# ETH_microSD.net
KiCad netlist of a schematic drawn in Altium Designer
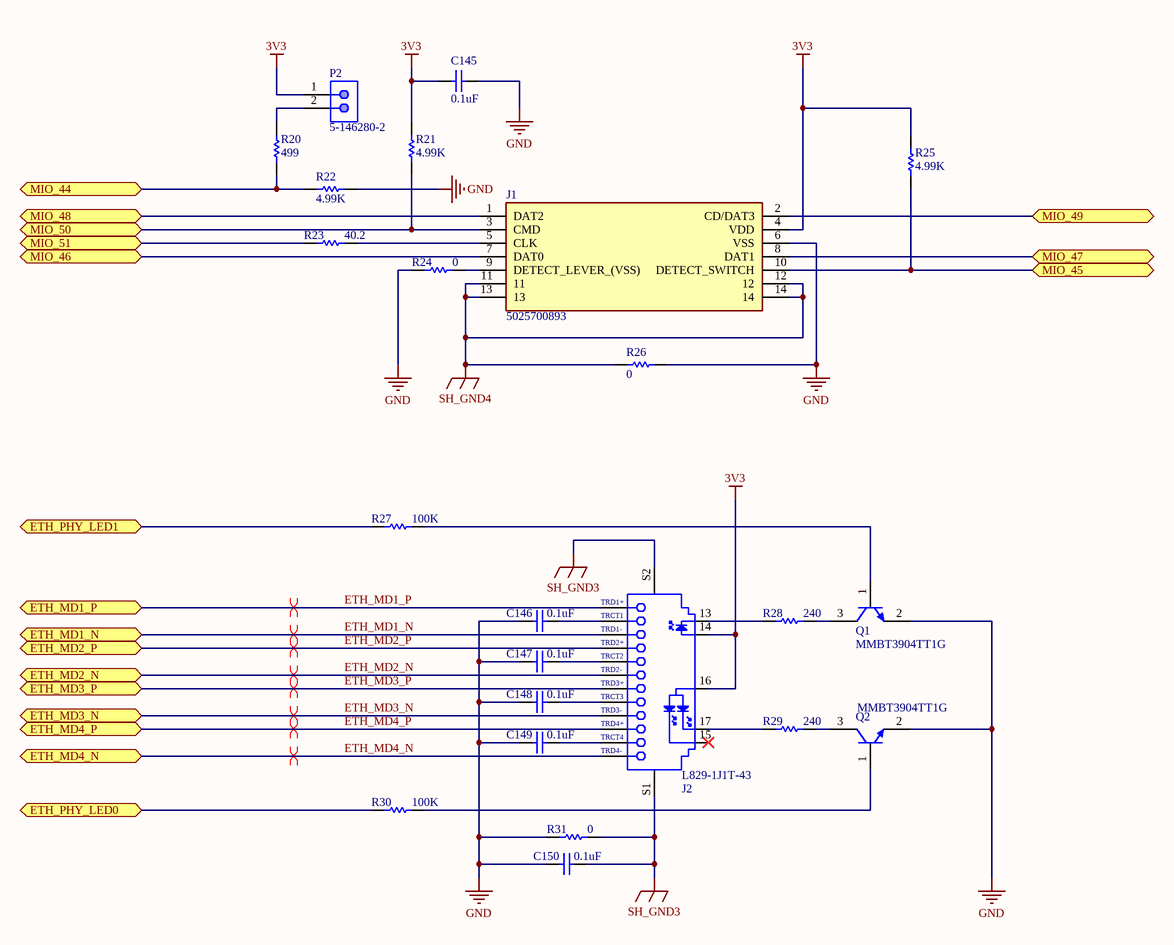
[diagram p0: ETH_microSD.SchDoc]

(export (version "E")
  (design (tool "Eeschema 10.0.6"))
  (components
    (comp (ref "C145")
      (value "0.1uF")
      (footprint "CAPC0201(0603)33_N")
      (libsource (lib "my_schsymbols") (part "CAP_0201"))
    )
    (comp (ref "C146")
      (value "0.1uF")
      (footprint "CAPC0201(0603)33_N")
      (libsource (lib "my_schsymbols") (part "CAP_0201"))
    )
    (comp (ref "C147")
      (value "0.1uF")
      (footprint "CAPC0201(0603)33_N")
      (libsource (lib "my_schsymbols") (part "CAP_0201"))
    )
    (comp (ref "C148")
      (value "0.1uF")
      (footprint "CAPC0201(0603)33_N")
      (libsource (lib "my_schsymbols") (part "CAP_0201"))
    )
    (comp (ref "C149")
      (value "0.1uF")
      (footprint "CAPC0201(0603)33_N")
      (libsource (lib "my_schsymbols") (part "CAP_0201"))
    )
    (comp (ref "C150")
      (value "0.1uF")
      (footprint "CAPC0201(0603)33_N")
      (libsource (lib "my_schsymbols") (part "CAP_0201"))
    )
    (comp (ref "J1")
      (value "5025700893")
      (footprint "5025700893")
      (description "Connector")
      (libsource (lib "altium-import") (part "root_0_5025700893_"))
    )
    (comp (ref "J2")
      (value "L829-1J1T-43")
      (footprint "BELS-L829-1J1T-43_V")
      (description "Gigabit MagJack(R) Ultra Low Profile, 10/100/1000 Base-T, 19-Pin THD, RoHS, Tray")
      (libsource (lib "Altium Content Vault") (part "RJ45-17-2SHLD"))
    )
    (comp (ref "P2")
      (value "5-146280-2")
      (footprint "TECO-5-146280-2_V")
      (fields (field (name "MANUFACTURER") "TE Connectivity"))
      (libsource (lib "Altium Content Vault") (part "CN-1P-M-R2"))
    )
    (comp (ref "Q1")
      (value "MMBT3904TT1G")
      (footprint "ONSC-SC-75-3-463-01_V")
      (description "General Purpose Transistor, NPN Silicon, 3-Pin SC-75, Pb-Free, Tape and Reel")
      (fields (field (name "MANUFACTURER") "On Semiconductor"))
      (libsource (lib "Altium Content Vault") (part "ONSC-NPN-B1E2C3-3"))
    )
    (comp (ref "Q2")
      (value "MMBT3904TT1G")
      (footprint "ONSC-SC-75-3-463-01_V")
      (description "General Purpose Transistor, NPN Silicon, 3-Pin SC-75, Pb-Free, Tape and Reel")
      (fields (field (name "MANUFACTURER") "On Semiconductor"))
      (libsource (lib "Altium Content Vault") (part "ONSC-NPN-B1E2C3-3"))
    )
    (comp (ref "R20")
      (value "499")
      (footprint "RESC0402(1005)_N")
      (libsource (lib "my_schsymbols") (part "RES_0402"))
    )
    (comp (ref "R21")
      (value "4.99K")
      (footprint "RESC0402(1005)_N")
      (libsource (lib "my_schsymbols") (part "RES_0402"))
    )
    (comp (ref "R22")
      (value "4.99K")
      (footprint "RESC0402(1005)_N")
      (libsource (lib "my_schsymbols") (part "RES_0402"))
    )
    (comp (ref "R23")
      (value "40.2")
      (footprint "RESC0402(1005)_N")
      (libsource (lib "my_schsymbols") (part "RES_0402"))
    )
    (comp (ref "R24")
      (value "0")
      (footprint "RESC0402(1005)_N")
      (libsource (lib "my_schsymbols") (part "RES_0402"))
    )
    (comp (ref "R25")
      (value "4.99K")
      (footprint "RESC0402(1005)_N")
      (libsource (lib "my_schsymbols") (part "RES_0402"))
    )
    (comp (ref "R26")
      (value "0")
      (footprint "RESC0402(1005)_N")
      (libsource (lib "my_schsymbols") (part "RES_0402"))
    )
    (comp (ref "R27")
      (value "100K")
      (footprint "RESC0402(1005)_N")
      (libsource (lib "my_schsymbols") (part "RES_0402"))
    )
    (comp (ref "R28")
      (value "240")
      (footprint "RESC0402(1005)_N")
      (libsource (lib "my_schsymbols") (part "RES_0402"))
    )
    (comp (ref "R29")
      (value "240")
      (footprint "RESC0402(1005)_N")
      (libsource (lib "my_schsymbols") (part "RES_0402"))
    )
    (comp (ref "R30")
      (value "100K")
      (footprint "RESC0402(1005)_N")
      (libsource (lib "my_schsymbols") (part "RES_0402"))
    )
    (comp (ref "R31")
      (value "0")
      (footprint "RESC0402(1005)_N")
      (libsource (lib "my_schsymbols") (part "RES_0402"))
    )
  )
  (nets
    (net (code "1") (name "/ETH_MD1_N") (class "Default")
      (node (ref "J2") (pin "3") (pinfunction "TRD1-_3") (pintype "passive"))
    )
    (net (code "2") (name "/ETH_MD1_P") (class "Default")
      (node (ref "J2") (pin "1") (pinfunction "TRD1+_1") (pintype "passive"))
    )
    (net (code "3") (name "/ETH_MD2_N") (class "Default")
      (node (ref "J2") (pin "6") (pinfunction "TRD2-_6") (pintype "passive"))
    )
    (net (code "4") (name "/ETH_MD2_P") (class "Default")
      (node (ref "J2") (pin "4") (pinfunction "TRD2+_4") (pintype "passive"))
    )
    (net (code "5") (name "/ETH_MD3_N") (class "Default")
      (node (ref "J2") (pin "9") (pinfunction "TRD3-_9") (pintype "passive"))
    )
    (net (code "6") (name "/ETH_MD3_P") (class "Default")
      (node (ref "J2") (pin "7") (pinfunction "TRD3+_7") (pintype "passive"))
    )
    (net (code "7") (name "/ETH_MD4_N") (class "Default")
      (node (ref "J2") (pin "12") (pinfunction "TRD4-_12") (pintype "passive"))
    )
    (net (code "8") (name "/ETH_MD4_P") (class "Default")
      (node (ref "J2") (pin "10") (pinfunction "TRD4+_10") (pintype "passive"))
    )
    (net (code "9") (name "/ETH_PHY_LED0") (class "Default")
      (node (ref "R30") (pin "1") (pinfunction "1_1") (pintype "passive"))
    )
    (net (code "10") (name "/ETH_PHY_LED1") (class "Default")
      (node (ref "R27") (pin "1") (pinfunction "1_1") (pintype "passive"))
    )
    (net (code "11") (name "/MIO_44") (class "Default")
      (node (ref "R20") (pin "1") (pinfunction "1_1") (pintype "passive"))
      (node (ref "R22") (pin "1") (pinfunction "1_1") (pintype "passive"))
    )
    (net (code "12") (name "/MIO_45") (class "Default")
      (node (ref "J1") (pin "10") (pinfunction "DETECT_SWITCH_10") (pintype "passive"))
      (node (ref "R25") (pin "1") (pinfunction "1_1") (pintype "passive"))
    )
    (net (code "13") (name "/MIO_46") (class "Default")
      (node (ref "J1") (pin "7") (pinfunction "DAT0_7") (pintype "passive"))
    )
    (net (code "14") (name "/MIO_47") (class "Default")
      (node (ref "J1") (pin "8") (pinfunction "DAT1_8") (pintype "passive"))
    )
    (net (code "15") (name "/MIO_48") (class "Default")
      (node (ref "J1") (pin "1") (pinfunction "DAT2_1") (pintype "passive"))
    )
    (net (code "16") (name "/MIO_49") (class "Default")
      (node (ref "J1") (pin "2") (pinfunction "CD/DAT3_2") (pintype "passive"))
    )
    (net (code "17") (name "/MIO_50") (class "Default")
      (node (ref "J1") (pin "3") (pinfunction "CMD_3") (pintype "passive"))
      (node (ref "R21") (pin "1") (pinfunction "1_1") (pintype "passive"))
    )
    (net (code "18") (name "/MIO_51") (class "Default")
      (node (ref "R23") (pin "1") (pinfunction "1_1") (pintype "passive"))
    )
    (net (code "19") (name "3V3") (class "Default")
      (node (ref "C145") (pin "1") (pinfunction "1_1") (pintype "passive"))
      (node (ref "J1") (pin "4") (pinfunction "VDD_4") (pintype "passive"))
      (node (ref "J2") (pin "14") (pinfunction "14_14") (pintype "passive"))
      (node (ref "J2") (pin "16") (pinfunction "16_16") (pintype "passive"))
      (node (ref "P2") (pin "1") (pinfunction "1_1") (pintype "passive"))
      (node (ref "R21") (pin "2") (pinfunction "2_2") (pintype "passive"))
      (node (ref "R25") (pin "2") (pinfunction "2_2") (pintype "passive"))
    )
    (net (code "20") (name "GND") (class "Default")
      (node (ref "C145") (pin "2") (pinfunction "2_2") (pintype "passive"))
      (node (ref "C146") (pin "1") (pinfunction "1_1") (pintype "passive"))
      (node (ref "C147") (pin "1") (pinfunction "1_1") (pintype "passive"))
      (node (ref "C148") (pin "1") (pinfunction "1_1") (pintype "passive"))
      (node (ref "C149") (pin "1") (pinfunction "1_1") (pintype "passive"))
      (node (ref "C150") (pin "1") (pinfunction "1_1") (pintype "passive"))
      (node (ref "J1") (pin "6") (pinfunction "VSS_6") (pintype "passive"))
      (node (ref "Q1") (pin "2") (pinfunction "E_2") (pintype "passive"))
      (node (ref "Q2") (pin "2") (pinfunction "E_2") (pintype "passive"))
      (node (ref "R22") (pin "2") (pinfunction "2_2") (pintype "passive"))
      (node (ref "R24") (pin "1") (pinfunction "1_1") (pintype "passive"))
      (node (ref "R26") (pin "2") (pinfunction "2_2") (pintype "passive"))
      (node (ref "R31") (pin "1") (pinfunction "1_1") (pintype "passive"))
    )
    (net (code "21") (name "Net-(J1-CLK)") (class "Default")
      (node (ref "J1") (pin "5") (pinfunction "CLK_5") (pintype "passive"))
      (node (ref "R23") (pin "2") (pinfunction "2_2") (pintype "passive"))
    )
    (net (code "22") (name "Net-(J1-DETECT_LEVER_(VSS))") (class "Default")
      (node (ref "J1") (pin "9") (pinfunction "DETECT_LEVER_(VSS)_9") (pintype "passive"))
      (node (ref "R24") (pin "2") (pinfunction "2_2") (pintype "passive"))
    )
    (net (code "23") (name "Net-(J2-Pad13)") (class "Default")
      (node (ref "J2") (pin "13") (pinfunction "13_13") (pintype "passive"))
      (node (ref "R28") (pin "1") (pinfunction "1_1") (pintype "passive"))
    )
    (net (code "24") (name "Net-(J2-Pad17)") (class "Default")
      (node (ref "J2") (pin "17") (pinfunction "17_17") (pintype "passive"))
      (node (ref "R29") (pin "1") (pinfunction "1_1") (pintype "passive"))
    )
    (net (code "25") (name "Net-(J2-TRCT1)") (class "Default")
      (node (ref "C146") (pin "2") (pinfunction "2_2") (pintype "passive"))
      (node (ref "J2") (pin "2") (pinfunction "TRCT1_2") (pintype "passive"))
    )
    (net (code "26") (name "Net-(J2-TRCT2)") (class "Default")
      (node (ref "C147") (pin "2") (pinfunction "2_2") (pintype "passive"))
      (node (ref "J2") (pin "5") (pinfunction "TRCT2_5") (pintype "passive"))
    )
    (net (code "27") (name "Net-(J2-TRCT3)") (class "Default")
      (node (ref "C148") (pin "2") (pinfunction "2_2") (pintype "passive"))
      (node (ref "J2") (pin "8") (pinfunction "TRCT3_8") (pintype "passive"))
    )
    (net (code "28") (name "Net-(J2-TRCT4)") (class "Default")
      (node (ref "C149") (pin "2") (pinfunction "2_2") (pintype "passive"))
      (node (ref "J2") (pin "11") (pinfunction "TRCT4_11") (pintype "passive"))
    )
    (net (code "29") (name "Net-(P2-Pad2)") (class "Default")
      (node (ref "P2") (pin "2") (pinfunction "2_2") (pintype "passive"))
      (node (ref "R20") (pin "2") (pinfunction "2_2") (pintype "passive"))
    )
    (net (code "30") (name "Net-(Q1-B)") (class "Default")
      (node (ref "Q1") (pin "1") (pinfunction "B_1") (pintype "passive"))
      (node (ref "R27") (pin "2") (pinfunction "2_2") (pintype "passive"))
    )
    (net (code "31") (name "Net-(Q1-C)") (class "Default")
      (node (ref "Q1") (pin "3") (pinfunction "C_3") (pintype "passive"))
      (node (ref "R28") (pin "2") (pinfunction "2_2") (pintype "passive"))
    )
    (net (code "32") (name "Net-(Q2-B)") (class "Default")
      (node (ref "Q2") (pin "1") (pinfunction "B_1") (pintype "passive"))
      (node (ref "R30") (pin "2") (pinfunction "2_2") (pintype "passive"))
    )
    (net (code "33") (name "Net-(Q2-C)") (class "Default")
      (node (ref "Q2") (pin "3") (pinfunction "C_3") (pintype "passive"))
      (node (ref "R29") (pin "2") (pinfunction "2_2") (pintype "passive"))
    )
    (net (code "34") (name "SH_GND3") (class "Default")
      (node (ref "C150") (pin "2") (pinfunction "2_2") (pintype "passive"))
      (node (ref "J2") (pin "S1") (pinfunction "S1_S1") (pintype "passive"))
      (node (ref "J2") (pin "S2") (pinfunction "S2_S2") (pintype "passive"))
      (node (ref "R31") (pin "2") (pinfunction "2_2") (pintype "passive"))
    )
    (net (code "35") (name "SH_GND4") (class "Default")
      (node (ref "J1") (pin "11") (pinfunction "11_11") (pintype "passive"))
      (node (ref "J1") (pin "12") (pinfunction "12_12") (pintype "passive"))
      (node (ref "J1") (pin "13") (pinfunction "13_13") (pintype "passive"))
      (node (ref "J1") (pin "14") (pinfunction "14_14") (pintype "passive"))
      (node (ref "R26") (pin "1") (pinfunction "1_1") (pintype "passive"))
    )
    (net (code "36") (name "unconnected-(J2-Pad15)") (class "Default")
      (node (ref "J2") (pin "15") (pinfunction "15_15") (pintype "passive+no_connect"))
    )
  )
)
